# catch_robo.net
KiCad netlist of a schematic drawn in EAGLE
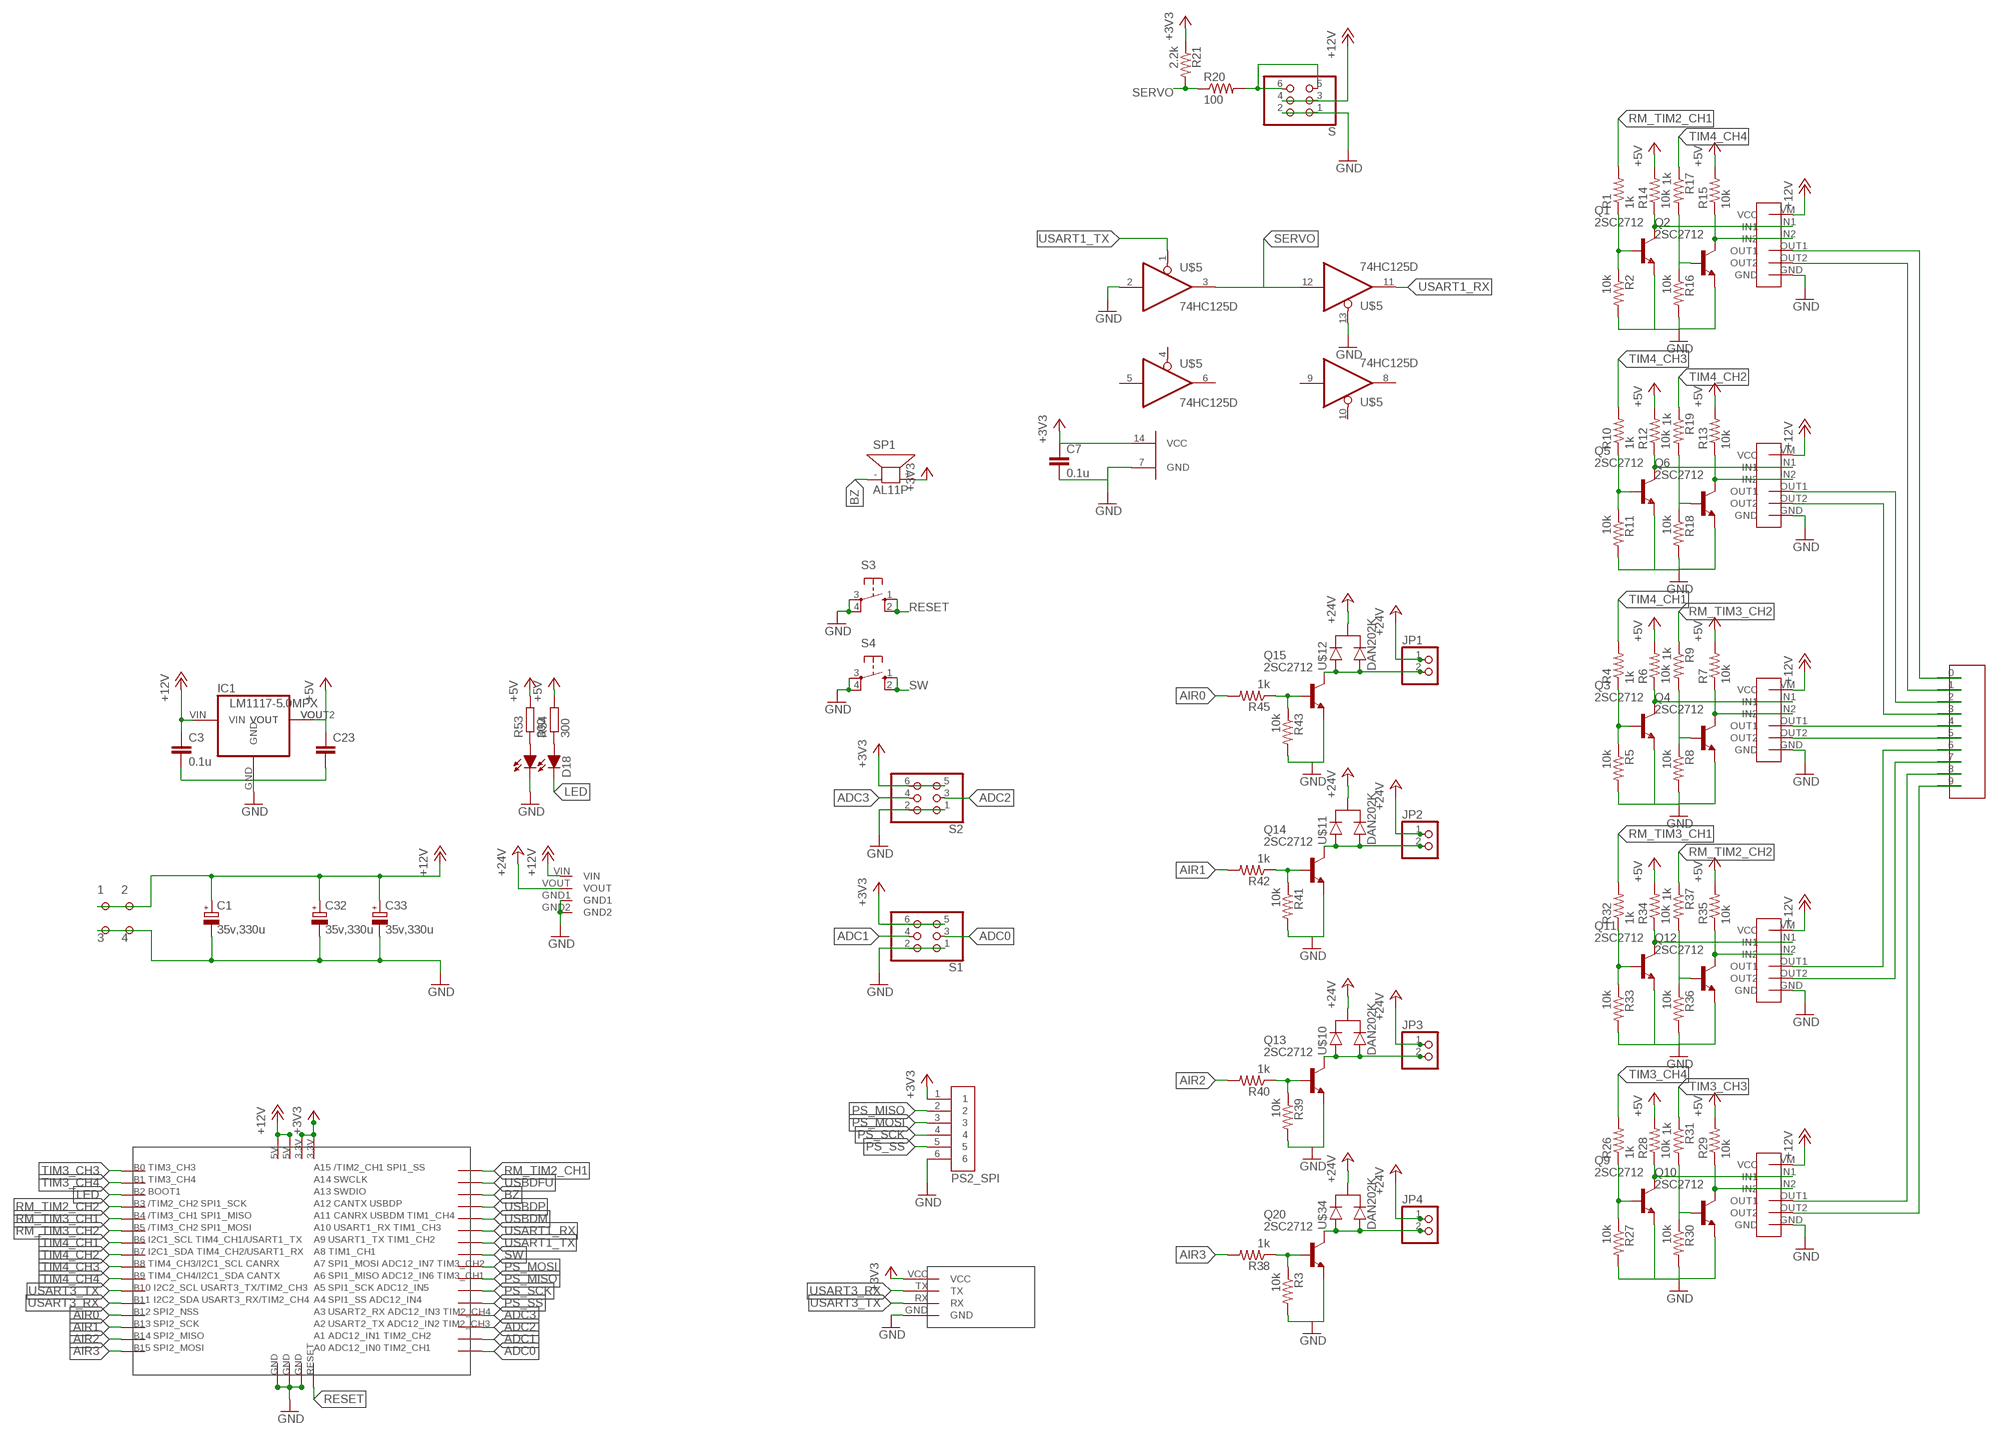
[diagram p0: schematic, sheet 1]

(export (version "E")
  (design (tool "Eeschema 10.0.6"))
  (components
    (comp (ref "C1")
      (value "35v,330u")
      (footprint "eagle-import:153CLV-1010")
      (libsource (lib "eagle-import") (part "CPOL-EU153CLV-1010"))
    )
    (comp (ref "C3")
      (value "0.1u")
      (footprint "eagle-import:C0603K")
      (libsource (lib "eagle-import") (part "resistor_C-EUC0603K"))
    )
    (comp (ref "C7")
      (value "0.1u")
      (footprint "eagle-import:C0603")
      (libsource (lib "eagle-import") (part "C-EUC0603"))
    )
    (comp (ref "C23")
      (value "C-EUC0603K")
      (footprint "eagle-import:C0603K")
      (libsource (lib "eagle-import") (part "resistor_C-EUC0603K"))
    )
    (comp (ref "C32")
      (value "35v,330u")
      (footprint "eagle-import:153CLV-1010")
      (libsource (lib "eagle-import") (part "CPOL-EU153CLV-1010"))
    )
    (comp (ref "C33")
      (value "35v,330u")
      (footprint "eagle-import:153CLV-1010")
      (libsource (lib "eagle-import") (part "CPOL-EU153CLV-1010"))
    )
    (comp (ref "D18")
      (value "SEC2XX4")
      (footprint "eagle-import:LED3025")
      (libsource (lib "eagle-import") (part "SEC2XX4"))
    )
    (comp (ref "IC1")
      (value "LM1117-5.0MPX")
      (footprint "eagle-import:SOT223")
      (libsource (lib "eagle-import") (part "LM1117IMP-5.0"))
    )
    (comp (ref "JP1")
      (value "PINHD-1X2/90")
      (footprint "eagle-import:1X02_90")
      (libsource (lib "eagle-import") (part "PINHD-1X2/90"))
    )
    (comp (ref "JP2")
      (value "PINHD-1X2/90")
      (footprint "eagle-import:1X02_90")
      (libsource (lib "eagle-import") (part "PINHD-1X2/90"))
    )
    (comp (ref "JP3")
      (value "PINHD-1X2/90")
      (footprint "eagle-import:1X02_90")
      (libsource (lib "eagle-import") (part "PINHD-1X2/90"))
    )
    (comp (ref "JP4")
      (value "PINHD-1X2/90")
      (footprint "eagle-import:1X02_90")
      (libsource (lib "eagle-import") (part "PINHD-1X2/90"))
    )
    (comp (ref "PS2_SPI")
      (value "CN6")
      (footprint "eagle-import:JST-B6B-XH-A")
      (libsource (lib "eagle-import") (part "CN6"))
    )
    (comp (ref "Q1")
      (value "2SC2712")
      (footprint "eagle-import:SC-59(TYPE1)")
      (libsource (lib "eagle-import") (part "2SC2712"))
    )
    (comp (ref "Q2")
      (value "2SC2712")
      (footprint "eagle-import:SC-59(TYPE1)")
      (libsource (lib "eagle-import") (part "2SC2712"))
    )
    (comp (ref "Q3")
      (value "2SC2712")
      (footprint "eagle-import:SC-59(TYPE1)")
      (libsource (lib "eagle-import") (part "2SC2712"))
    )
    (comp (ref "Q4")
      (value "2SC2712")
      (footprint "eagle-import:SC-59(TYPE1)")
      (libsource (lib "eagle-import") (part "2SC2712"))
    )
    (comp (ref "Q5")
      (value "2SC2712")
      (footprint "eagle-import:SC-59(TYPE1)")
      (libsource (lib "eagle-import") (part "2SC2712"))
    )
    (comp (ref "Q6")
      (value "2SC2712")
      (footprint "eagle-import:SC-59(TYPE1)")
      (libsource (lib "eagle-import") (part "2SC2712"))
    )
    (comp (ref "Q9")
      (value "2SC2712")
      (footprint "eagle-import:SC-59(TYPE1)")
      (libsource (lib "eagle-import") (part "2SC2712"))
    )
    (comp (ref "Q10")
      (value "2SC2712")
      (footprint "eagle-import:SC-59(TYPE1)")
      (libsource (lib "eagle-import") (part "2SC2712"))
    )
    (comp (ref "Q11")
      (value "2SC2712")
      (footprint "eagle-import:SC-59(TYPE1)")
      (libsource (lib "eagle-import") (part "2SC2712"))
    )
    (comp (ref "Q12")
      (value "2SC2712")
      (footprint "eagle-import:SC-59(TYPE1)")
      (libsource (lib "eagle-import") (part "2SC2712"))
    )
    (comp (ref "Q13")
      (value "2SC2712")
      (footprint "eagle-import:SC-59(TYPE1)")
      (libsource (lib "eagle-import") (part "2SC2712"))
    )
    (comp (ref "Q14")
      (value "2SC2712")
      (footprint "eagle-import:SC-59(TYPE1)")
      (libsource (lib "eagle-import") (part "2SC2712"))
    )
    (comp (ref "Q15")
      (value "2SC2712")
      (footprint "eagle-import:SC-59(TYPE1)")
      (libsource (lib "eagle-import") (part "2SC2712"))
    )
    (comp (ref "Q20")
      (value "2SC2712")
      (footprint "eagle-import:SC-59(TYPE1)")
      (libsource (lib "eagle-import") (part "2SC2712"))
    )
    (comp (ref "R1")
      (value "1k")
      (footprint "eagle-import:R0603")
      (libsource (lib "eagle-import") (part "R-US_R0603"))
    )
    (comp (ref "R2")
      (value "10k")
      (footprint "eagle-import:R0603")
      (libsource (lib "eagle-import") (part "R-US_R0603"))
    )
    (comp (ref "R3")
      (value "10k")
      (footprint "eagle-import:R0603")
      (libsource (lib "eagle-import") (part "R-US_R0603"))
    )
    (comp (ref "R4")
      (value "1k")
      (footprint "eagle-import:R0603")
      (libsource (lib "eagle-import") (part "R-US_R0603"))
    )
    (comp (ref "R5")
      (value "10k")
      (footprint "eagle-import:R0603")
      (libsource (lib "eagle-import") (part "R-US_R0603"))
    )
    (comp (ref "R6")
      (value "10k")
      (footprint "eagle-import:R0603")
      (libsource (lib "eagle-import") (part "R-US_R0603"))
    )
    (comp (ref "R7")
      (value "10k")
      (footprint "eagle-import:R0603")
      (libsource (lib "eagle-import") (part "R-US_R0603"))
    )
    (comp (ref "R8")
      (value "10k")
      (footprint "eagle-import:R0603")
      (libsource (lib "eagle-import") (part "R-US_R0603"))
    )
    (comp (ref "R9")
      (value "1k")
      (footprint "eagle-import:R0603")
      (libsource (lib "eagle-import") (part "R-US_R0603"))
    )
    (comp (ref "R10")
      (value "1k")
      (footprint "eagle-import:R0603")
      (libsource (lib "eagle-import") (part "R-US_R0603"))
    )
    (comp (ref "R11")
      (value "10k")
      (footprint "eagle-import:R0603")
      (libsource (lib "eagle-import") (part "R-US_R0603"))
    )
    (comp (ref "R12")
      (value "10k")
      (footprint "eagle-import:R0603")
      (libsource (lib "eagle-import") (part "R-US_R0603"))
    )
    (comp (ref "R13")
      (value "10k")
      (footprint "eagle-import:R0603")
      (libsource (lib "eagle-import") (part "R-US_R0603"))
    )
    (comp (ref "R14")
      (value "10k")
      (footprint "eagle-import:R0603")
      (libsource (lib "eagle-import") (part "R-US_R0603"))
    )
    (comp (ref "R15")
      (value "10k")
      (footprint "eagle-import:R0603")
      (libsource (lib "eagle-import") (part "R-US_R0603"))
    )
    (comp (ref "R16")
      (value "10k")
      (footprint "eagle-import:R0603")
      (libsource (lib "eagle-import") (part "R-US_R0603"))
    )
    (comp (ref "R17")
      (value "1k")
      (footprint "eagle-import:R0603")
      (libsource (lib "eagle-import") (part "R-US_R0603"))
    )
    (comp (ref "R18")
      (value "10k")
      (footprint "eagle-import:R0603")
      (libsource (lib "eagle-import") (part "R-US_R0603"))
    )
    (comp (ref "R19")
      (value "1k")
      (footprint "eagle-import:R0603")
      (libsource (lib "eagle-import") (part "R-US_R0603"))
    )
    (comp (ref "R20")
      (value "100")
      (footprint "eagle-import:R0603")
      (libsource (lib "eagle-import") (part "R-US_R0603"))
    )
    (comp (ref "R21")
      (value "2.2k")
      (footprint "eagle-import:R0603")
      (libsource (lib "eagle-import") (part "R-US_R0603"))
    )
    (comp (ref "R26")
      (value "1k")
      (footprint "eagle-import:R0603")
      (libsource (lib "eagle-import") (part "R-US_R0603"))
    )
    (comp (ref "R27")
      (value "10k")
      (footprint "eagle-import:R0603")
      (libsource (lib "eagle-import") (part "R-US_R0603"))
    )
    (comp (ref "R28")
      (value "10k")
      (footprint "eagle-import:R0603")
      (libsource (lib "eagle-import") (part "R-US_R0603"))
    )
    (comp (ref "R29")
      (value "10k")
      (footprint "eagle-import:R0603")
      (libsource (lib "eagle-import") (part "R-US_R0603"))
    )
    (comp (ref "R30")
      (value "10k")
      (footprint "eagle-import:R0603")
      (libsource (lib "eagle-import") (part "R-US_R0603"))
    )
    (comp (ref "R31")
      (value "1k")
      (footprint "eagle-import:R0603")
      (libsource (lib "eagle-import") (part "R-US_R0603"))
    )
    (comp (ref "R32")
      (value "1k")
      (footprint "eagle-import:R0603")
      (libsource (lib "eagle-import") (part "R-US_R0603"))
    )
    (comp (ref "R33")
      (value "10k")
      (footprint "eagle-import:R0603")
      (libsource (lib "eagle-import") (part "R-US_R0603"))
    )
    (comp (ref "R34")
      (value "10k")
      (footprint "eagle-import:R0603")
      (libsource (lib "eagle-import") (part "R-US_R0603"))
    )
    (comp (ref "R35")
      (value "10k")
      (footprint "eagle-import:R0603")
      (libsource (lib "eagle-import") (part "R-US_R0603"))
    )
    (comp (ref "R36")
      (value "10k")
      (footprint "eagle-import:R0603")
      (libsource (lib "eagle-import") (part "R-US_R0603"))
    )
    (comp (ref "R37")
      (value "1k")
      (footprint "eagle-import:R0603")
      (libsource (lib "eagle-import") (part "R-US_R0603"))
    )
    (comp (ref "R38")
      (value "1k")
      (footprint "eagle-import:R0603")
      (libsource (lib "eagle-import") (part "R-US_R0603"))
    )
    (comp (ref "R39")
      (value "10k")
      (footprint "eagle-import:R0603")
      (libsource (lib "eagle-import") (part "R-US_R0603"))
    )
    (comp (ref "R40")
      (value "1k")
      (footprint "eagle-import:R0603")
      (libsource (lib "eagle-import") (part "R-US_R0603"))
    )
    (comp (ref "R41")
      (value "10k")
      (footprint "eagle-import:R0603")
      (libsource (lib "eagle-import") (part "R-US_R0603"))
    )
    (comp (ref "R42")
      (value "1k")
      (footprint "eagle-import:R0603")
      (libsource (lib "eagle-import") (part "R-US_R0603"))
    )
    (comp (ref "R43")
      (value "10k")
      (footprint "eagle-import:R0603")
      (libsource (lib "eagle-import") (part "R-US_R0603"))
    )
    (comp (ref "R45")
      (value "1k")
      (footprint "eagle-import:R0603")
      (libsource (lib "eagle-import") (part "R-US_R0603"))
    )
    (comp (ref "R53")
      (value "300")
      (footprint "eagle-import:R0603")
      (libsource (lib "eagle-import") (part "R-EU_R0603"))
    )
    (comp (ref "R54")
      (value "300")
      (footprint "eagle-import:R0603")
      (libsource (lib "eagle-import") (part "R-EU_R0603"))
    )
    (comp (ref "S")
      (value "PINHD-2X3/90")
      (footprint "eagle-import:2X03_90")
      (libsource (lib "eagle-import") (part "PINHD-2X3/90"))
    )
    (comp (ref "S1")
      (value "PINHD-2X3/90")
      (footprint "eagle-import:2X03_90")
      (libsource (lib "eagle-import") (part "PINHD-2X3/90"))
    )
    (comp (ref "S2")
      (value "PINHD-2X3/90")
      (footprint "eagle-import:2X03_90")
      (libsource (lib "eagle-import") (part "PINHD-2X3/90"))
    )
    (comp (ref "S3")
      (value "10-XX")
      (footprint "eagle-import:B3F-10XX")
      (fields (field (name "MPN") "B3F-1000"))
      (libsource (lib "eagle-import") (part "10-XX"))
    )
    (comp (ref "S4")
      (value "10-XX")
      (footprint "eagle-import:B3F-10XX")
      (fields (field (name "MPN") "B3F-1000"))
      (libsource (lib "eagle-import") (part "10-XX"))
    )
    (comp (ref "SP1")
      (value "AL11P")
      (footprint "eagle-import:AL11P")
      (libsource (lib "eagle-import") (part "AL11P"))
    )
    (comp (ref "U$1")
      (value "STBE_MINI")
      (footprint "eagle-import:STBEE_MINI")
      (libsource (lib "eagle-import") (part "STBE_MINI"))
    )
    (comp (ref "U$2")
      (value "TB6643")
      (footprint "eagle-import:TB6643")
      (libsource (lib "eagle-import") (part "TB6643"))
    )
    (comp (ref "U$3")
      (value "TB6643")
      (footprint "eagle-import:TB6643")
      (libsource (lib "eagle-import") (part "TB6643"))
    )
    (comp (ref "U$4")
      (value "TB6643")
      (footprint "eagle-import:TB6643")
      (libsource (lib "eagle-import") (part "TB6643"))
    )
    (comp (ref "U$5")
      (value "74HC125D")
      (footprint "eagle-import:SO14")
      (libsource (lib "eagle-import") (part "74HC125D"))
    )
    (comp (ref "U$6")
      (value "TB6643")
      (footprint "eagle-import:TB6643")
      (libsource (lib "eagle-import") (part "TB6643"))
    )
    (comp (ref "U$7")
      (value "TB6643")
      (footprint "eagle-import:TB6643")
      (libsource (lib "eagle-import") (part "TB6643"))
    )
    (comp (ref "U$8")
      (value "ML-40")
      (footprint "eagle-import:ML-40")
      (libsource (lib "eagle-import") (part "ML-40"))
    )
    (comp (ref "U$9")
      (value "LT3580")
      (footprint "eagle-import:LT3580")
      (libsource (lib "eagle-import") (part "LT3580"))
    )
    (comp (ref "U$10")
      (value "DAN202K")
      (footprint "eagle-import:SC-59")
      (libsource (lib "eagle-import") (part "DAN202K"))
    )
    (comp (ref "U$11")
      (value "DAN202K")
      (footprint "eagle-import:SC-59")
      (libsource (lib "eagle-import") (part "DAN202K"))
    )
    (comp (ref "U$12")
      (value "DAN202K")
      (footprint "eagle-import:SC-59")
      (libsource (lib "eagle-import") (part "DAN202K"))
    )
    (comp (ref "U$13")
      (value "5569")
      (footprint "eagle-import:5569")
      (libsource (lib "eagle-import") (part "5569"))
    )
    (comp (ref "U$14")
      (value "XBEE_2.54")
      (footprint "eagle-import:XBEE_2.54")
      (libsource (lib "eagle-import") (part "XBEE_2.54"))
    )
    (comp (ref "U$34")
      (value "DAN202K")
      (footprint "eagle-import:SC-59")
      (libsource (lib "eagle-import") (part "DAN202K"))
    )
  )
  (nets
    (net (code "1") (name "+3V3") (class "Default")
      (node (ref "C7") (pin "1") (pinfunction "1_1") (pintype "passive"))
      (node (ref "PS2_SPI") (pin "1") (pinfunction "1_1") (pintype "passive"))
      (node (ref "R21") (pin "1") (pinfunction "1_1") (pintype "passive"))
      (node (ref "S1") (pin "5") (pinfunction "5_5") (pintype "passive"))
      (node (ref "S1") (pin "6") (pinfunction "6_6") (pintype "passive"))
      (node (ref "S2") (pin "5") (pinfunction "5_5") (pintype "passive"))
      (node (ref "S2") (pin "6") (pinfunction "6_6") (pintype "passive"))
      (node (ref "SP1") (pin "+") (pinfunction "2_+") (pintype "passive"))
      (node (ref "U$1") (pin "3.3V1") (pinfunction "3.3V1_3.3V1") (pintype "bidirectional"))
      (node (ref "U$1") (pin "3.3V2") (pinfunction "3.3V2_3.3V2") (pintype "bidirectional"))
      (node (ref "U$14") (pin "VCC") (pinfunction "VCC_VCC") (pintype "bidirectional"))
      (node (ref "U$5") (pin "14") (pinfunction "VCC_14") (pintype "bidirectional"))
    )
    (net (code "2") (name "+5V") (class "Default")
      (node (ref "C23") (pin "1") (pinfunction "1_1") (pintype "passive"))
      (node (ref "IC1") (pin "VOUT") (pinfunction "VOUT_VOUT") (pintype "output"))
      (node (ref "IC1") (pin "VOUT2") (pinfunction "VOUT_VOUT2") (pintype "output"))
      (node (ref "R12") (pin "2") (pinfunction "2_2") (pintype "passive"))
      (node (ref "R13") (pin "2") (pinfunction "2_2") (pintype "passive"))
      (node (ref "R14") (pin "2") (pinfunction "2_2") (pintype "passive"))
      (node (ref "R15") (pin "2") (pinfunction "2_2") (pintype "passive"))
      (node (ref "R28") (pin "2") (pinfunction "2_2") (pintype "passive"))
      (node (ref "R29") (pin "2") (pinfunction "2_2") (pintype "passive"))
      (node (ref "R34") (pin "2") (pinfunction "2_2") (pintype "passive"))
      (node (ref "R35") (pin "2") (pinfunction "2_2") (pintype "passive"))
      (node (ref "R53") (pin "2") (pinfunction "2_2") (pintype "passive"))
      (node (ref "R54") (pin "2") (pinfunction "2_2") (pintype "passive"))
      (node (ref "R6") (pin "2") (pinfunction "2_2") (pintype "passive"))
      (node (ref "R7") (pin "2") (pinfunction "2_2") (pintype "passive"))
    )
    (net (code "3") (name "+12V") (class "Default")
      (node (ref "C1") (pin "+") (pinfunction "+_+") (pintype "passive"))
      (node (ref "C3") (pin "1") (pinfunction "1_1") (pintype "passive"))
      (node (ref "C32") (pin "+") (pinfunction "+_+") (pintype "passive"))
      (node (ref "C33") (pin "+") (pinfunction "+_+") (pintype "passive"))
      (node (ref "IC1") (pin "VIN") (pinfunction "VIN_VIN") (pintype "input"))
      (node (ref "S") (pin "3") (pinfunction "3_3") (pintype "passive"))
      (node (ref "S") (pin "4") (pinfunction "4_4") (pintype "passive"))
      (node (ref "U$1") (pin "5V1") (pinfunction "5V1_5V1") (pintype "bidirectional"))
      (node (ref "U$1") (pin "5V2") (pinfunction "5V2_5V2") (pintype "bidirectional"))
      (node (ref "U$13") (pin "1") (pinfunction "1_1") (pintype "bidirectional"))
      (node (ref "U$13") (pin "2") (pinfunction "2_2") (pintype "bidirectional"))
      (node (ref "U$2") (pin "VM") (pinfunction "VCC_VM") (pintype "bidirectional"))
      (node (ref "U$3") (pin "VM") (pinfunction "VCC_VM") (pintype "bidirectional"))
      (node (ref "U$4") (pin "VM") (pinfunction "VCC_VM") (pintype "bidirectional"))
      (node (ref "U$6") (pin "VM") (pinfunction "VCC_VM") (pintype "bidirectional"))
      (node (ref "U$7") (pin "VM") (pinfunction "VCC_VM") (pintype "bidirectional"))
      (node (ref "U$9") (pin "VIN") (pinfunction "VIN_VIN") (pintype "bidirectional"))
    )
    (net (code "4") (name "+24V") (class "Default")
      (node (ref "JP1") (pin "1") (pinfunction "1_1") (pintype "passive"))
      (node (ref "JP2") (pin "1") (pinfunction "1_1") (pintype "passive"))
      (node (ref "JP3") (pin "1") (pinfunction "1_1") (pintype "passive"))
      (node (ref "JP4") (pin "1") (pinfunction "1_1") (pintype "passive"))
      (node (ref "U$10") (pin "K") (pinfunction "K_K") (pintype "passive"))
      (node (ref "U$11") (pin "K") (pinfunction "K_K") (pintype "passive"))
      (node (ref "U$12") (pin "K") (pinfunction "K_K") (pintype "passive"))
      (node (ref "U$34") (pin "K") (pinfunction "K_K") (pintype "passive"))
      (node (ref "U$9") (pin "VOUT") (pinfunction "VOUT_VOUT") (pintype "bidirectional"))
    )
    (net (code "5") (name "ADC0") (class "Default")
      (node (ref "S1") (pin "3") (pinfunction "3_3") (pintype "passive"))
      (node (ref "U$1") (pin "A0") (pinfunction "A0_A0") (pintype "bidirectional"))
    )
    (net (code "6") (name "ADC1") (class "Default")
      (node (ref "S1") (pin "4") (pinfunction "4_4") (pintype "passive"))
      (node (ref "U$1") (pin "A1") (pinfunction "A1_A1") (pintype "bidirectional"))
    )
    (net (code "7") (name "ADC2") (class "Default")
      (node (ref "S2") (pin "3") (pinfunction "3_3") (pintype "passive"))
      (node (ref "U$1") (pin "A2") (pinfunction "A2_A2") (pintype "bidirectional"))
    )
    (net (code "8") (name "ADC3") (class "Default")
      (node (ref "S2") (pin "4") (pinfunction "4_4") (pintype "passive"))
      (node (ref "U$1") (pin "A3") (pinfunction "A3_A3") (pintype "bidirectional"))
    )
    (net (code "9") (name "AIR0") (class "Default")
      (node (ref "R45") (pin "2") (pinfunction "2_2") (pintype "passive"))
      (node (ref "U$1") (pin "B12") (pinfunction "B12_B12") (pintype "bidirectional"))
    )
    (net (code "10") (name "AIR1") (class "Default")
      (node (ref "R42") (pin "2") (pinfunction "2_2") (pintype "passive"))
      (node (ref "U$1") (pin "B13") (pinfunction "B13_B13") (pintype "bidirectional"))
    )
    (net (code "11") (name "AIR2") (class "Default")
      (node (ref "R40") (pin "2") (pinfunction "2_2") (pintype "passive"))
      (node (ref "U$1") (pin "B14") (pinfunction "B14_B14") (pintype "bidirectional"))
    )
    (net (code "12") (name "AIR3") (class "Default")
      (node (ref "R38") (pin "2") (pinfunction "2_2") (pintype "passive"))
      (node (ref "U$1") (pin "B15") (pinfunction "B15_B15") (pintype "bidirectional"))
    )
    (net (code "13") (name "BZ") (class "Default")
      (node (ref "SP1") (pin "-") (pinfunction "1_-") (pintype "passive"))
      (node (ref "U$1") (pin "A13") (pinfunction "A13_A13") (pintype "bidirectional"))
    )
    (net (code "14") (name "GND") (class "Default")
      (node (ref "C1") (pin "-") (pinfunction "-_-") (pintype "passive"))
      (node (ref "C23") (pin "2") (pinfunction "2_2") (pintype "passive"))
      (node (ref "C3") (pin "2") (pinfunction "2_2") (pintype "passive"))
      (node (ref "C32") (pin "-") (pinfunction "-_-") (pintype "passive"))
      (node (ref "C33") (pin "-") (pinfunction "-_-") (pintype "passive"))
      (node (ref "C7") (pin "2") (pinfunction "2_2") (pintype "passive"))
      (node (ref "D18") (pin "2") (pinfunction "C1_2") (pintype "passive"))
      (node (ref "IC1") (pin "GND") (pinfunction "GND_GND") (pintype "power_in"))
      (node (ref "PS2_SPI") (pin "6") (pinfunction "6_6") (pintype "passive"))
      (node (ref "Q1") (pin "E") (pinfunction "E_E") (pintype "passive"))
      (node (ref "Q10") (pin "E") (pinfunction "E_E") (pintype "passive"))
      (node (ref "Q11") (pin "E") (pinfunction "E_E") (pintype "passive"))
      (node (ref "Q12") (pin "E") (pinfunction "E_E") (pintype "passive"))
      (node (ref "Q13") (pin "E") (pinfunction "E_E") (pintype "passive"))
      (node (ref "Q14") (pin "E") (pinfunction "E_E") (pintype "passive"))
      (node (ref "Q15") (pin "E") (pinfunction "E_E") (pintype "passive"))
      (node (ref "Q2") (pin "E") (pinfunction "E_E") (pintype "passive"))
      (node (ref "Q20") (pin "E") (pinfunction "E_E") (pintype "passive"))
      (node (ref "Q3") (pin "E") (pinfunction "E_E") (pintype "passive"))
      (node (ref "Q4") (pin "E") (pinfunction "E_E") (pintype "passive"))
      (node (ref "Q5") (pin "E") (pinfunction "E_E") (pintype "passive"))
      (node (ref "Q6") (pin "E") (pinfunction "E_E") (pintype "passive"))
      (node (ref "Q9") (pin "E") (pinfunction "E_E") (pintype "passive"))
      (node (ref "R11") (pin "2") (pinfunction "2_2") (pintype "passive"))
      (node (ref "R16") (pin "2") (pinfunction "2_2") (pintype "passive"))
      (node (ref "R18") (pin "2") (pinfunction "2_2") (pintype "passive"))
      (node (ref "R2") (pin "2") (pinfunction "2_2") (pintype "passive"))
      (node (ref "R27") (pin "2") (pinfunction "2_2") (pintype "passive"))
      (node (ref "R3") (pin "2") (pinfunction "2_2") (pintype "passive"))
      (node (ref "R30") (pin "2") (pinfunction "2_2") (pintype "passive"))
      (node (ref "R33") (pin "2") (pinfunction "2_2") (pintype "passive"))
      (node (ref "R36") (pin "2") (pinfunction "2_2") (pintype "passive"))
      (node (ref "R39") (pin "2") (pinfunction "2_2") (pintype "passive"))
      (node (ref "R41") (pin "2") (pinfunction "2_2") (pintype "passive"))
      (node (ref "R43") (pin "2") (pinfunction "2_2") (pintype "passive"))
      (node (ref "R5") (pin "2") (pinfunction "2_2") (pintype "passive"))
      (node (ref "R8") (pin "2") (pinfunction "2_2") (pintype "passive"))
      (node (ref "S") (pin "1") (pinfunction "1_1") (pintype "passive"))
      (node (ref "S") (pin "2") (pinfunction "2_2") (pintype "passive"))
      (node (ref "S1") (pin "1") (pinfunction "1_1") (pintype "passive"))
      (node (ref "S1") (pin "2") (pinfunction "2_2") (pintype "passive"))
      (node (ref "S2") (pin "1") (pinfunction "1_1") (pintype "passive"))
      (node (ref "S2") (pin "2") (pinfunction "2_2") (pintype "passive"))
      (node (ref "S3") (pin "3") (pinfunction "P_3") (pintype "passive"))
      (node (ref "S3") (pin "4") (pinfunction "P1_4") (pintype "passive"))
      (node (ref "S4") (pin "3") (pinfunction "P_3") (pintype "passive"))
      (node (ref "S4") (pin "4") (pinfunction "P1_4") (pintype "passive"))
      (node (ref "U$1") (pin "GND1") (pinfunction "GND1_GND1") (pintype "bidirectional"))
      (node (ref "U$1") (pin "GND2") (pinfunction "GND2_GND2") (pintype "bidirectional"))
      (node (ref "U$1") (pin "GND3") (pinfunction "GND3_GND3") (pintype "bidirectional"))
      (node (ref "U$13") (pin "3") (pinfunction "3_3") (pintype "bidirectional"))
      (node (ref "U$13") (pin "4") (pinfunction "4_4") (pintype "bidirectional"))
      (node (ref "U$14") (pin "GND") (pinfunction "GND_GND") (pintype "bidirectional"))
      (node (ref "U$2") (pin "GND") (pinfunction "GND_GND") (pintype "bidirectional"))
      (node (ref "U$3") (pin "GND") (pinfunction "GND_GND") (pintype "bidirectional"))
      (node (ref "U$4") (pin "GND") (pinfunction "GND_GND") (pintype "bidirectional"))
      (node (ref "U$5") (pin "13") (pinfunction "4OE_13") (pintype "input"))
      (node (ref "U$5") (pin "2") (pinfunction "1A_2") (pintype "input"))
      (node (ref "U$5") (pin "7") (pinfunction "GND_7") (pintype "bidirectional"))
      (node (ref "U$6") (pin "GND") (pinfunction "GND_GND") (pintype "bidirectional"))
      (node (ref "U$7") (pin "GND") (pinfunction "GND_GND") (pintype "bidirectional"))
      (node (ref "U$9") (pin "GND1") (pinfunction "GND1_GND1") (pintype "bidirectional"))
      (node (ref "U$9") (pin "GND2") (pinfunction "GND2_GND2") (pintype "bidirectional"))
    )
    (net (code "15") (name "LED") (class "Default")
      (node (ref "D18") (pin "1") (pinfunction "C0_1") (pintype "passive"))
      (node (ref "U$1") (pin "B2") (pinfunction "B2_B2") (pintype "bidirectional"))
    )
    (net (code "16") (name "Net-(D18-A0)") (class "Default")
      (node (ref "D18") (pin "4") (pinfunction "A0_4") (pintype "passive"))
      (node (ref "R54") (pin "1") (pinfunction "1_1") (pintype "passive"))
    )
    (net (code "17") (name "Net-(D18-A1)") (class "Default")
      (node (ref "D18") (pin "3") (pinfunction "A1_3") (pintype "passive"))
      (node (ref "R53") (pin "1") (pinfunction "1_1") (pintype "passive"))
    )
    (net (code "18") (name "Net-(Q1-PadB)") (class "Default")
      (node (ref "Q1") (pin "B") (pinfunction "B_B") (pintype "passive"))
      (node (ref "R1") (pin "1") (pinfunction "1_1") (pintype "passive"))
      (node (ref "R2") (pin "1") (pinfunction "1_1") (pintype "passive"))
    )
    (net (code "19") (name "Net-(Q1-PadC)") (class "Default")
      (node (ref "Q1") (pin "C") (pinfunction "C_C") (pintype "passive"))
      (node (ref "R14") (pin "1") (pinfunction "1_1") (pintype "passive"))
      (node (ref "U$2") (pin "IN1") (pinfunction "IN1_IN1") (pintype "bidirectional"))
    )
    (net (code "20") (name "Net-(Q2-PadB)") (class "Default")
      (node (ref "Q2") (pin "B") (pinfunction "B_B") (pintype "passive"))
      (node (ref "R16") (pin "1") (pinfunction "1_1") (pintype "passive"))
      (node (ref "R17") (pin "2") (pinfunction "2_2") (pintype "passive"))
    )
    (net (code "21") (name "Net-(Q2-PadC)") (class "Default")
      (node (ref "Q2") (pin "C") (pinfunction "C_C") (pintype "passive"))
      (node (ref "R15") (pin "1") (pinfunction "1_1") (pintype "passive"))
      (node (ref "U$2") (pin "IN2") (pinfunction "IN2_IN2") (pintype "bidirectional"))
    )
    (net (code "22") (name "Net-(Q3-PadB)") (class "Default")
      (node (ref "Q3") (pin "B") (pinfunction "B_B") (pintype "passive"))
      (node (ref "R4") (pin "1") (pinfunction "1_1") (pintype "passive"))
      (node (ref "R5") (pin "1") (pinfunction "1_1") (pintype "passive"))
    )
    (net (code "23") (name "Net-(Q3-PadC)") (class "Default")
      (node (ref "Q3") (pin "C") (pinfunction "C_C") (pintype "passive"))
      (node (ref "R6") (pin "1") (pinfunction "1_1") (pintype "passive"))
      (node (ref "U$3") (pin "IN1") (pinfunction "IN1_IN1") (pintype "bidirectional"))
    )
    (net (code "24") (name "Net-(Q4-PadB)") (class "Default")
      (node (ref "Q4") (pin "B") (pinfunction "B_B") (pintype "passive"))
      (node (ref "R8") (pin "1") (pinfunction "1_1") (pintype "passive"))
      (node (ref "R9") (pin "2") (pinfunction "2_2") (pintype "passive"))
    )
    (net (code "25") (name "Net-(Q4-PadC)") (class "Default")
      (node (ref "Q4") (pin "C") (pinfunction "C_C") (pintype "passive"))
      (node (ref "R7") (pin "1") (pinfunction "1_1") (pintype "passive"))
      (node (ref "U$3") (pin "IN2") (pinfunction "IN2_IN2") (pintype "bidirectional"))
    )
    (net (code "26") (name "Net-(Q5-PadB)") (class "Default")
      (node (ref "Q5") (pin "B") (pinfunction "B_B") (pintype "passive"))
      (node (ref "R10") (pin "1") (pinfunction "1_1") (pintype "passive"))
      (node (ref "R11") (pin "1") (pinfunction "1_1") (pintype "passive"))
    )
    (net (code "27") (name "Net-(Q5-PadC)") (class "Default")
      (node (ref "Q5") (pin "C") (pinfunction "C_C") (pintype "passive"))
      (node (ref "R12") (pin "1") (pinfunction "1_1") (pintype "passive"))
      (node (ref "U$4") (pin "IN1") (pinfunction "IN1_IN1") (pintype "bidirectional"))
    )
    (net (code "28") (name "Net-(Q6-PadB)") (class "Default")
      (node (ref "Q6") (pin "B") (pinfunction "B_B") (pintype "passive"))
      (node (ref "R18") (pin "1") (pinfunction "1_1") (pintype "passive"))
      (node (ref "R19") (pin "2") (pinfunction "2_2") (pintype "passive"))
    )
    (net (code "29") (name "Net-(Q6-PadC)") (class "Default")
      (node (ref "Q6") (pin "C") (pinfunction "C_C") (pintype "passive"))
      (node (ref "R13") (pin "1") (pinfunction "1_1") (pintype "passive"))
      (node (ref "U$4") (pin "IN2") (pinfunction "IN2_IN2") (pintype "bidirectional"))
    )
    (net (code "30") (name "Net-(Q9-PadB)") (class "Default")
      (node (ref "Q9") (pin "B") (pinfunction "B_B") (pintype "passive"))
      (node (ref "R26") (pin "1") (pinfunction "1_1") (pintype "passive"))
      (node (ref "R27") (pin "1") (pinfunction "1_1") (pintype "passive"))
    )
    (net (code "31") (name "Net-(Q9-PadC)") (class "Default")
      (node (ref "Q9") (pin "C") (pinfunction "C_C") (pintype "passive"))
      (node (ref "R28") (pin "1") (pinfunction "1_1") (pintype "passive"))
      (node (ref "U$6") (pin "IN1") (pinfunction "IN1_IN1") (pintype "bidirectional"))
    )
    (net (code "32") (name "Net-(Q10-PadB)") (class "Default")
      (node (ref "Q10") (pin "B") (pinfunction "B_B") (pintype "passive"))
      (node (ref "R30") (pin "1") (pinfunction "1_1") (pintype "passive"))
      (node (ref "R31") (pin "2") (pinfunction "2_2") (pintype "passive"))
    )
    (net (code "33") (name "Net-(Q10-PadC)") (class "Default")
      (node (ref "Q10") (pin "C") (pinfunction "C_C") (pintype "passive"))
      (node (ref "R29") (pin "1") (pinfunction "1_1") (pintype "passive"))
      (node (ref "U$6") (pin "IN2") (pinfunction "IN2_IN2") (pintype "bidirectional"))
    )
    (net (code "34") (name "Net-(Q11-PadB)") (class "Default")
      (node (ref "Q11") (pin "B") (pinfunction "B_B") (pintype "passive"))
      (node (ref "R32") (pin "1") (pinfunction "1_1") (pintype "passive"))
      (node (ref "R33") (pin "1") (pinfunction "1_1") (pintype "passive"))
    )
    (net (code "35") (name "Net-(Q11-PadC)") (class "Default")
      (node (ref "Q11") (pin "C") (pinfunction "C_C") (pintype "passive"))
      (node (ref "R34") (pin "1") (pinfunction "1_1") (pintype "passive"))
      (node (ref "U$7") (pin "IN1") (pinfunction "IN1_IN1") (pintype "bidirectional"))
    )
    (net (code "36") (name "Net-(Q12-PadB)") (class "Default")
      (node (ref "Q12") (pin "B") (pinfunction "B_B") (pintype "passive"))
      (node (ref "R36") (pin "1") (pinfunction "1_1") (pintype "passive"))
      (node (ref "R37") (pin "2") (pinfunction "2_2") (pintype "passive"))
    )
    (net (code "37") (name "Net-(Q12-PadC)") (class "Default")
      (node (ref "Q12") (pin "C") (pinfunction "C_C") (pintype "passive"))
      (node (ref "R35") (pin "1") (pinfunction "1_1") (pintype "passive"))
      (node (ref "U$7") (pin "IN2") (pinfunction "IN2_IN2") (pintype "bidirectional"))
    )
    (net (code "38") (name "Net-(Q13-PadB)") (class "Default")
      (node (ref "Q13") (pin "B") (pinfunction "B_B") (pintype "passive"))
      (node (ref "R39") (pin "1") (pinfunction "1_1") (pintype "passive"))
      (node (ref "R40") (pin "1") (pinfunction "1_1") (pintype "passive"))
    )
    (net (code "39") (name "Net-(Q14-PadB)") (class "Default")
      (node (ref "Q14") (pin "B") (pinfunction "B_B") (pintype "passive"))
      (node (ref "R41") (pin "1") (pinfunction "1_1") (pintype "passive"))
      (node (ref "R42") (pin "1") (pinfunction "1_1") (pintype "passive"))
    )
    (net (code "40") (name "Net-(Q15-PadB)") (class "Default")
      (node (ref "Q15") (pin "B") (pinfunction "B_B") (pintype "passive"))
      (node (ref "R43") (pin "1") (pinfunction "1_1") (pintype "passive"))
      (node (ref "R45") (pin "1") (pinfunction "1_1") (pintype "passive"))
    )
    (net (code "41") (name "Net-(Q20-PadB)") (class "Default")
      (node (ref "Q20") (pin "B") (pinfunction "B_B") (pintype "passive"))
      (node (ref "R3") (pin "1") (pinfunction "1_1") (pintype "passive"))
      (node (ref "R38") (pin "1") (pinfunction "1_1") (pintype "passive"))
    )
    (net (code "42") (name "Net-(R20-Pad2)") (class "Default")
      (node (ref "R20") (pin "2") (pinfunction "2_2") (pintype "passive"))
      (node (ref "S") (pin "5") (pinfunction "5_5") (pintype "passive"))
      (node (ref "S") (pin "6") (pinfunction "6_6") (pintype "passive"))
    )
    (net (code "43") (name "Net-(U$2-PadOUT1)") (class "Default")
      (node (ref "U$2") (pin "OUT1") (pinfunction "OUT1_OUT1") (pintype "bidirectional"))
      (node (ref "U$8") (pin "0") (pinfunction "0_0") (pintype "bidirectional"))
    )
    (net (code "44") (name "Net-(U$2-PadOUT2)") (class "Default")
      (node (ref "U$2") (pin "OUT2") (pinfunction "OUT2_OUT2") (pintype "bidirectional"))
      (node (ref "U$8") (pin "1") (pinfunction "1_1") (pintype "bidirectional"))
    )
    (net (code "45") (name "Net-(U$3-PadOUT1)") (class "Default")
      (node (ref "U$3") (pin "OUT1") (pinfunction "OUT1_OUT1") (pintype "bidirectional"))
      (node (ref "U$8") (pin "4") (pinfunction "4_4") (pintype "bidirectional"))
    )
    (net (code "46") (name "Net-(U$3-PadOUT2)") (class "Default")
      (node (ref "U$3") (pin "OUT2") (pinfunction "OUT2_OUT2") (pintype "bidirectional"))
      (node (ref "U$8") (pin "5") (pinfunction "5_5") (pintype "bidirectional"))
    )
    (net (code "47") (name "Net-(U$4-PadOUT1)") (class "Default")
      (node (ref "U$4") (pin "OUT1") (pinfunction "OUT1_OUT1") (pintype "bidirectional"))
      (node (ref "U$8") (pin "2") (pinfunction "2_2") (pintype "bidirectional"))
    )
    (net (code "48") (name "Net-(U$4-PadOUT2)") (class "Default")
      (node (ref "U$4") (pin "OUT2") (pinfunction "OUT2_OUT2") (pintype "bidirectional"))
      (node (ref "U$8") (pin "3") (pinfunction "3_3") (pintype "bidirectional"))
    )
    (net (code "49") (name "Net-(U$6-PadOUT1)") (class "Default")
      (node (ref "U$6") (pin "OUT1") (pinfunction "OUT1_OUT1") (pintype "bidirectional"))
      (node (ref "U$8") (pin "8") (pinfunction "8_8") (pintype "bidirectional"))
    )
    (net (code "50") (name "Net-(U$6-PadOUT2)") (class "Default")
      (node (ref "U$6") (pin "OUT2") (pinfunction "OUT2_OUT2") (pintype "bidirectional"))
      (node (ref "U$8") (pin "9") (pinfunction "9_9") (pintype "bidirectional"))
    )
    (net (code "51") (name "Net-(U$7-PadOUT1)") (class "Default")
      (node (ref "U$7") (pin "OUT1") (pinfunction "OUT1_OUT1") (pintype "bidirectional"))
      (node (ref "U$8") (pin "6") (pinfunction "6_6") (pintype "bidirectional"))
    )
    (net (code "52") (name "Net-(U$7-PadOUT2)") (class "Default")
      (node (ref "U$7") (pin "OUT2") (pinfunction "OUT2_OUT2") (pintype "bidirectional"))
      (node (ref "U$8") (pin "7") (pinfunction "7_7") (pintype "bidirectional"))
    )
    (net (code "53") (name "Net-(U$10-A1)") (class "Default")
      (node (ref "JP3") (pin "2") (pinfunction "2_2") (pintype "passive"))
      (node (ref "Q13") (pin "C") (pinfunction "C_C") (pintype "passive"))
      (node (ref "U$10") (pin "A@1") (pinfunction "A1_A@1") (pintype "passive"))
      (node (ref "U$10") (pin "A@2") (pinfunction "A2_A@2") (pintype "passive"))
    )
    (net (code "54") (name "Net-(U$11-A1)") (class "Default")
      (node (ref "JP2") (pin "2") (pinfunction "2_2") (pintype "passive"))
      (node (ref "Q14") (pin "C") (pinfunction "C_C") (pintype "passive"))
      (node (ref "U$11") (pin "A@1") (pinfunction "A1_A@1") (pintype "passive"))
      (node (ref "U$11") (pin "A@2") (pinfunction "A2_A@2") (pintype "passive"))
    )
    (net (code "55") (name "Net-(U$12-A1)") (class "Default")
      (node (ref "JP1") (pin "2") (pinfunction "2_2") (pintype "passive"))
      (node (ref "Q15") (pin "C") (pinfunction "C_C") (pintype "passive"))
      (node (ref "U$12") (pin "A@1") (pinfunction "A1_A@1") (pintype "passive"))
      (node (ref "U$12") (pin "A@2") (pinfunction "A2_A@2") (pintype "passive"))
    )
    (net (code "56") (name "Net-(U$34-A1)") (class "Default")
      (node (ref "JP4") (pin "2") (pinfunction "2_2") (pintype "passive"))
      (node (ref "Q20") (pin "C") (pinfunction "C_C") (pintype "passive"))
      (node (ref "U$34") (pin "A@1") (pinfunction "A1_A@1") (pintype "passive"))
      (node (ref "U$34") (pin "A@2") (pinfunction "A2_A@2") (pintype "passive"))
    )
    (net (code "57") (name "PS_MISO") (class "Default")
      (node (ref "PS2_SPI") (pin "2") (pinfunction "2_2") (pintype "passive"))
      (node (ref "U$1") (pin "A6") (pinfunction "A6_A6") (pintype "bidirectional"))
    )
    (net (code "58") (name "PS_MOSI") (class "Default")
      (node (ref "PS2_SPI") (pin "3") (pinfunction "3_3") (pintype "passive"))
      (node (ref "U$1") (pin "A7") (pinfunction "A7_A7") (pintype "bidirectional"))
    )
    (net (code "59") (name "PS_SCK") (class "Default")
      (node (ref "PS2_SPI") (pin "4") (pinfunction "4_4") (pintype "passive"))
      (node (ref "U$1") (pin "A5") (pinfunction "A5_A5") (pintype "bidirectional"))
    )
    (net (code "60") (name "PS_SS") (class "Default")
      (node (ref "PS2_SPI") (pin "5") (pinfunction "5_5") (pintype "passive"))
      (node (ref "U$1") (pin "A4") (pinfunction "A4_A4") (pintype "bidirectional"))
    )
    (net (code "61") (name "RESET") (class "Default")
      (node (ref "S3") (pin "1") (pinfunction "S_1") (pintype "passive"))
      (node (ref "S3") (pin "2") (pinfunction "S1_2") (pintype "passive"))
      (node (ref "U$1") (pin "RESET") (pinfunction "RESET_RESET") (pintype "bidirectional"))
    )
    (net (code "62") (name "RM_TIM2_CH1") (class "Default")
      (node (ref "R1") (pin "2") (pinfunction "2_2") (pintype "passive"))
      (node (ref "U$1") (pin "A15") (pinfunction "A15_A15") (pintype "bidirectional"))
    )
    (net (code "63") (name "RM_TIM2_CH2") (class "Default")
      (node (ref "R37") (pin "1") (pinfunction "1_1") (pintype "passive"))
      (node (ref "U$1") (pin "B3") (pinfunction "B3_B3") (pintype "bidirectional"))
    )
    (net (code "64") (name "RM_TIM3_CH1") (class "Default")
      (node (ref "R32") (pin "2") (pinfunction "2_2") (pintype "passive"))
      (node (ref "U$1") (pin "B4") (pinfunction "B4_B4") (pintype "bidirectional"))
    )
    (net (code "65") (name "RM_TIM3_CH2") (class "Default")
      (node (ref "R9") (pin "1") (pinfunction "1_1") (pintype "passive"))
      (node (ref "U$1") (pin "B5") (pinfunction "B5_B5") (pintype "bidirectional"))
    )
    (net (code "66") (name "SERVO") (class "Default")
      (node (ref "R20") (pin "1") (pinfunction "1_1") (pintype "passive"))
      (node (ref "R21") (pin "2") (pinfunction "2_2") (pintype "passive"))
      (node (ref "U$5") (pin "12") (pinfunction "4A_12") (pintype "input"))
      (node (ref "U$5") (pin "3") (pinfunction "1Y_3") (pintype "tri_state"))
    )
    (net (code "67") (name "SW") (class "Default")
      (node (ref "S4") (pin "1") (pinfunction "S_1") (pintype "passive"))
      (node (ref "S4") (pin "2") (pinfunction "S1_2") (pintype "passive"))
      (node (ref "U$1") (pin "A8") (pinfunction "A8_A8") (pintype "bidirectional"))
    )
    (net (code "68") (name "TIM3_CH3") (class "Default")
      (node (ref "R31") (pin "1") (pinfunction "1_1") (pintype "passive"))
      (node (ref "U$1") (pin "B0") (pinfunction "B0_B0") (pintype "bidirectional"))
    )
    (net (code "69") (name "TIM3_CH4") (class "Default")
      (node (ref "R26") (pin "2") (pinfunction "2_2") (pintype "passive"))
      (node (ref "U$1") (pin "B1") (pinfunction "B1_B1") (pintype "bidirectional"))
    )
    (net (code "70") (name "TIM4_CH1") (class "Default")
      (node (ref "R4") (pin "2") (pinfunction "2_2") (pintype "passive"))
      (node (ref "U$1") (pin "B6") (pinfunction "B6_B6") (pintype "bidirectional"))
    )
    (net (code "71") (name "TIM4_CH2") (class "Default")
      (node (ref "R19") (pin "1") (pinfunction "1_1") (pintype "passive"))
      (node (ref "U$1") (pin "B7") (pinfunction "B7_B7") (pintype "bidirectional"))
    )
    (net (code "72") (name "TIM4_CH3") (class "Default")
      (node (ref "R10") (pin "2") (pinfunction "2_2") (pintype "passive"))
      (node (ref "U$1") (pin "B8") (pinfunction "B8_B8") (pintype "bidirectional"))
    )
    (net (code "73") (name "TIM4_CH4") (class "Default")
      (node (ref "R17") (pin "1") (pinfunction "1_1") (pintype "passive"))
      (node (ref "U$1") (pin "B9") (pinfunction "B9_B9") (pintype "bidirectional"))
    )
    (net (code "74") (name "USART1_RX") (class "Default")
      (node (ref "U$1") (pin "A10") (pinfunction "A10_A10") (pintype "bidirectional"))
      (node (ref "U$5") (pin "11") (pinfunction "4Y_11") (pintype "tri_state"))
    )
    (net (code "75") (name "USART1_TX") (class "Default")
      (node (ref "U$1") (pin "A9") (pinfunction "A9_A9") (pintype "bidirectional"))
      (node (ref "U$5") (pin "1") (pinfunction "1OE_1") (pintype "input"))
    )
    (net (code "76") (name "USART3_RX") (class "Default")
      (node (ref "U$1") (pin "B11") (pinfunction "B11_B11") (pintype "bidirectional"))
      (node (ref "U$14") (pin "TX") (pinfunction "TX_TX") (pintype "bidirectional"))
    )
    (net (code "77") (name "USART3_TX") (class "Default")
      (node (ref "U$1") (pin "B10") (pinfunction "B10_B10") (pintype "bidirectional"))
      (node (ref "U$14") (pin "RX") (pinfunction "RX_RX") (pintype "bidirectional"))
    )
    (net (code "78") (name "USBDFU") (class "Default")
      (node (ref "U$1") (pin "A14") (pinfunction "A14_A14") (pintype "bidirectional"))
    )
    (net (code "79") (name "USBDM") (class "Default")
      (node (ref "U$1") (pin "A11") (pinfunction "A11_A11") (pintype "bidirectional"))
    )
    (net (code "80") (name "USBDP") (class "Default")
      (node (ref "U$1") (pin "A12") (pinfunction "A12_A12") (pintype "bidirectional"))
    )
    (net (code "81") (name "unconnected-(U$5-2A-Pad5)") (class "Default")
      (node (ref "U$5") (pin "5") (pinfunction "2A_5") (pintype "input"))
    )
    (net (code "82") (name "unconnected-(U$5-2OE-Pad4)") (class "Default")
      (node (ref "U$5") (pin "4") (pinfunction "2OE_4") (pintype "input"))
    )
    (net (code "83") (name "unconnected-(U$5-2Y-Pad6)") (class "Default")
      (node (ref "U$5") (pin "6") (pinfunction "2Y_6") (pintype "tri_state"))
    )
    (net (code "84") (name "unconnected-(U$5-3A-Pad9)") (class "Default")
      (node (ref "U$5") (pin "9") (pinfunction "3A_9") (pintype "input"))
    )
    (net (code "85") (name "unconnected-(U$5-3OE-Pad10)") (class "Default")
      (node (ref "U$5") (pin "10") (pinfunction "3OE_10") (pintype "input"))
    )
    (net (code "86") (name "unconnected-(U$5-3Y-Pad8)") (class "Default")
      (node (ref "U$5") (pin "8") (pinfunction "3Y_8") (pintype "tri_state"))
    )
  )
)
